# esquematico.net
KiCad netlist of a schematic drawn in Altium Designer
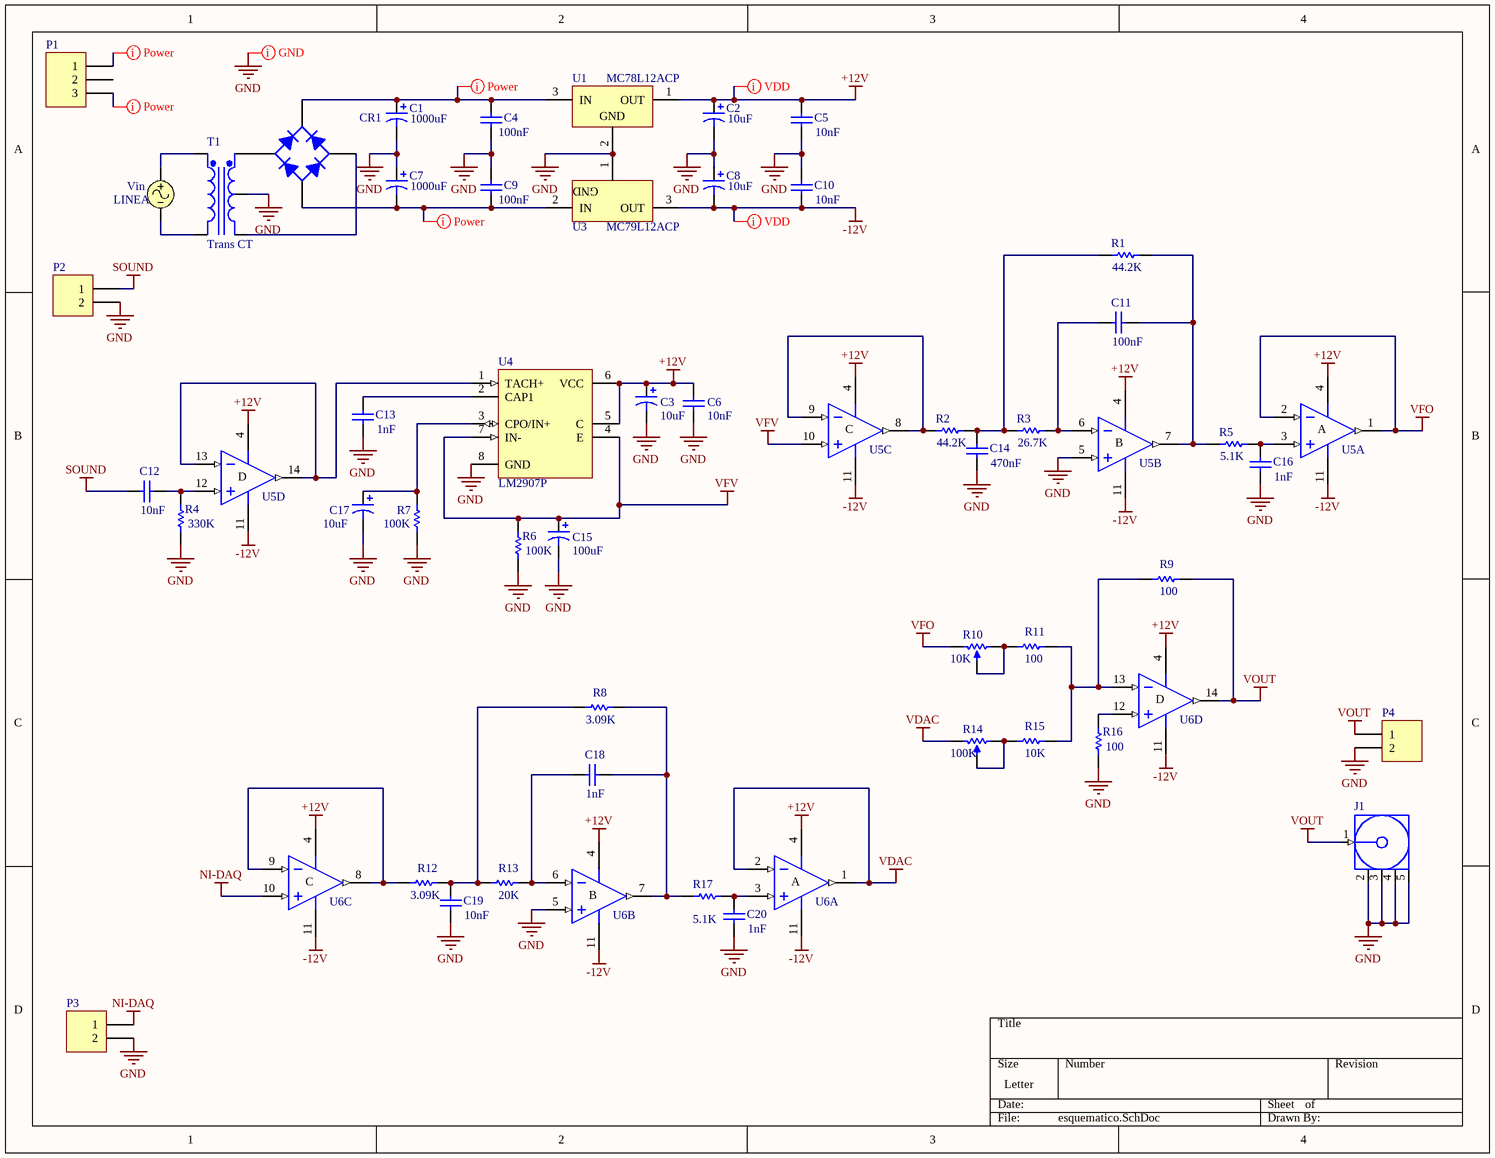
[diagram p0: esquematico.SchDoc]

(export (version "E")
  (design (tool "Eeschema 10.0.6"))
  (components
    (comp (ref "C1")
      (value "1000uF")
      (footprint "CAPPR5-10x20/H1.1")
      (description "Polarized Capacitor (Radial)")
      (fields (field (name "Comment") "Cap Pol1") (field (name "PUBLISHER") "Altium Limited"))
      (libsource (lib "Miscellaneous Devices") (part "Cap Pol1"))
    )
    (comp (ref "C2")
      (value "10uF")
      (footprint "CAPPR2-5x11")
      (description "Polarized Capacitor (Radial)")
      (fields (field (name "Comment") "Cap Pol1") (field (name "PUBLISHER") "Altium Limited"))
      (libsource (lib "Miscellaneous Devices") (part "Cap Pol1"))
    )
    (comp (ref "C3")
      (value "10uF")
      (footprint "CAPPR2-5x11")
      (description "Polarized Capacitor (Radial)")
      (fields (field (name "Comment") "Cap Pol1") (field (name "PUBLISHER") "Altium Limited"))
      (libsource (lib "Miscellaneous Devices") (part "Cap Pol1"))
    )
    (comp (ref "C4")
      (value "100nF")
      (footprint "CAPR2.54-4x2.5")
      (description "Capacitor")
      (fields (field (name "Comment") "Cap") (field (name "PUBLISHER") "Altium Limited"))
      (libsource (lib "Miscellaneous Devices") (part "Cap"))
    )
    (comp (ref "C5")
      (value "10nF")
      (footprint "CAPR2.54-4x2.5")
      (description "Capacitor")
      (fields (field (name "Comment") "Cap") (field (name "PUBLISHER") "Altium Limited"))
      (libsource (lib "Miscellaneous Devices") (part "Cap"))
    )
    (comp (ref "C6")
      (value "10nF")
      (footprint "CAPR2.54-4x2.5")
      (description "Capacitor")
      (fields (field (name "Comment") "Cap") (field (name "PUBLISHER") "Altium Limited"))
      (libsource (lib "Miscellaneous Devices") (part "Cap"))
    )
    (comp (ref "C7")
      (value "1000uF")
      (footprint "CAPPR5-10x20/H1.1")
      (description "Polarized Capacitor (Radial)")
      (fields (field (name "Comment") "Cap Pol1") (field (name "PUBLISHER") "Altium Limited"))
      (libsource (lib "Miscellaneous Devices") (part "Cap Pol1"))
    )
    (comp (ref "C8")
      (value "10uF")
      (footprint "CAPPR2-5x11")
      (description "Polarized Capacitor (Radial)")
      (fields (field (name "Comment") "Cap Pol1") (field (name "PUBLISHER") "Altium Limited"))
      (libsource (lib "Miscellaneous Devices") (part "Cap Pol1"))
    )
    (comp (ref "C9")
      (value "100nF")
      (footprint "CAPR2.54-4x2.5")
      (description "Capacitor")
      (fields (field (name "Comment") "Cap") (field (name "PUBLISHER") "Altium Limited"))
      (libsource (lib "Miscellaneous Devices") (part "Cap"))
    )
    (comp (ref "C10")
      (value "10nF")
      (footprint "CAPR2.54-4x2.5")
      (description "Capacitor")
      (fields (field (name "Comment") "Cap") (field (name "PUBLISHER") "Altium Limited"))
      (libsource (lib "Miscellaneous Devices") (part "Cap"))
    )
    (comp (ref "C11")
      (value "100nF")
      (footprint "CAPR2.54-4x2.5")
      (description "Capacitor")
      (fields (field (name "Comment") "Cap") (field (name "PUBLISHER") "Altium Limited"))
      (libsource (lib "Miscellaneous Devices") (part "Cap"))
    )
    (comp (ref "C12")
      (value "10nF")
      (footprint "CAPR2.54-4x2.5")
      (description "Capacitor")
      (fields (field (name "Comment") "Cap") (field (name "PUBLISHER") "Altium Limited"))
      (libsource (lib "Miscellaneous Devices") (part "Cap"))
    )
    (comp (ref "C13")
      (value "1nF")
      (footprint "CAPR5.08-4x2.5")
      (description "Capacitor")
      (fields (field (name "Comment") "Cap") (field (name "PUBLISHER") "Altium Limited"))
      (libsource (lib "Miscellaneous Devices") (part "Cap"))
    )
    (comp (ref "C14")
      (value "470nF")
      (footprint "CAPR5.08-4x2.5")
      (description "Capacitor")
      (fields (field (name "Comment") "Cap") (field (name "PUBLISHER") "Altium Limited"))
      (libsource (lib "Miscellaneous Devices") (part "Cap"))
    )
    (comp (ref "C15")
      (value "100uF")
      (footprint "CAPPR2.5-6.3x11")
      (description "Polarized Capacitor (Radial)")
      (fields (field (name "Comment") "Cap Pol1") (field (name "PUBLISHER") "Altium Limited"))
      (libsource (lib "Miscellaneous Devices") (part "Cap Pol1"))
    )
    (comp (ref "C16")
      (value "1nF")
      (footprint "CAPR5.08-5.1x2.5")
      (description "Capacitor")
      (fields (field (name "Comment") "Cap") (field (name "PUBLISHER") "Altium Limited"))
      (libsource (lib "Miscellaneous Devices") (part "Cap"))
    )
    (comp (ref "C17")
      (value "10uF")
      (footprint "CAPPR2-5x11")
      (description "Polarized Capacitor (Radial)")
      (fields (field (name "Comment") "Cap Pol1") (field (name "PUBLISHER") "Altium Limited"))
      (libsource (lib "Miscellaneous Devices") (part "Cap Pol1"))
    )
    (comp (ref "C18")
      (value "1nF")
      (footprint "CAPR5.08-5.1x2.5")
      (description "Capacitor")
      (fields (field (name "Comment") "Cap") (field (name "PUBLISHER") "Altium Limited"))
      (libsource (lib "Miscellaneous Devices") (part "Cap"))
    )
    (comp (ref "C19")
      (value "10nF")
      (footprint "CAPR2.54-4x2.5")
      (description "Capacitor")
      (fields (field (name "Comment") "Cap") (field (name "PUBLISHER") "Altium Limited"))
      (libsource (lib "Miscellaneous Devices") (part "Cap"))
    )
    (comp (ref "C20")
      (value "1nF")
      (footprint "CAPR5.08-5.1x2.5")
      (description "Capacitor")
      (fields (field (name "Comment") "Cap") (field (name "PUBLISHER") "Altium Limited"))
      (libsource (lib "Miscellaneous Devices") (part "Cap"))
    )
    (comp (ref "CR1")
      (value "2KBP005")
      (footprint "D-44")
      (description "2 Amp Single Phase Rectifier Bridge")
      (fields (field (name "PUBLISHER") "Altium Limited"))
      (libsource (lib "IR Rectifier - Bridge") (part "2KBP005"))
    )
    (comp (ref "J1")
      (value "COAX-F")
      (footprint "MCX5.08-H5")
      (fields (field (name "PUBLISHER") "Altium Limited"))
      (libsource (lib "Miscellaneous Connectors") (part "COAX-F"))
    )
    (comp (ref "P1")
      (value "Header 3")
      (footprint "HDR1X3")
      (description "Header, 3-Pin")
      (fields (field (name "PUBLISHER") "Altium Limited"))
      (libsource (lib "Miscellaneous Connectors") (part "Header 3"))
    )
    (comp (ref "P2")
      (value "Header 2")
      (footprint "HDR1X2")
      (description "Header, 2-Pin")
      (fields (field (name "PUBLISHER") "Altium Limited"))
      (libsource (lib "") (part "Header 2_1"))
    )
    (comp (ref "P3")
      (value "Header 2")
      (footprint "HDR1X2")
      (description "Header, 2-Pin")
      (fields (field (name "PUBLISHER") "Altium Limited"))
      (libsource (lib "") (part "Header 2_1"))
    )
    (comp (ref "P4")
      (value "Header 2")
      (footprint "HDR1X2")
      (description "Header, 2-Pin")
      (fields (field (name "PUBLISHER") "Altium Limited"))
      (libsource (lib "Miscellaneous Connectors") (part "Header 2"))
    )
    (comp (ref "R1")
      (value "44.2K")
      (footprint "AXIAL-0.3")
      (description "Resistor")
      (fields (field (name "Comment") "Res1") (field (name "PUBLISHER") "Altium Limited"))
      (libsource (lib "Miscellaneous Devices") (part "Res1"))
    )
    (comp (ref "R2")
      (value "44.2K")
      (footprint "AXIAL-0.3")
      (description "Resistor")
      (fields (field (name "Comment") "Res1") (field (name "PUBLISHER") "Altium Limited"))
      (libsource (lib "Miscellaneous Devices") (part "Res1"))
    )
    (comp (ref "R3")
      (value "26.7K")
      (footprint "AXIAL-0.3")
      (description "Resistor")
      (fields (field (name "Comment") "Res1") (field (name "PUBLISHER") "Altium Limited"))
      (libsource (lib "Miscellaneous Devices") (part "Res1"))
    )
    (comp (ref "R4")
      (value "330K")
      (footprint "AXIAL-0.3")
      (description "Resistor")
      (fields (field (name "Comment") "Res1") (field (name "PUBLISHER") "Altium Limited"))
      (libsource (lib "Miscellaneous Devices") (part "Res1"))
    )
    (comp (ref "R5")
      (value "5.1K")
      (footprint "AXIAL-0.3")
      (description "Resistor")
      (fields (field (name "Comment") "Res1") (field (name "PUBLISHER") "Altium Limited"))
      (libsource (lib "Miscellaneous Devices") (part "Res1"))
    )
    (comp (ref "R6")
      (value "100K")
      (footprint "AXIAL-0.3")
      (description "Resistor")
      (fields (field (name "Comment") "Res1") (field (name "PUBLISHER") "Altium Limited"))
      (libsource (lib "Miscellaneous Devices") (part "Res1"))
    )
    (comp (ref "R7")
      (value "100K")
      (footprint "AXIAL-0.3")
      (description "Resistor")
      (fields (field (name "Comment") "Res1") (field (name "PUBLISHER") "Altium Limited"))
      (libsource (lib "Miscellaneous Devices") (part "Res1"))
    )
    (comp (ref "R8")
      (value "3.09K")
      (footprint "AXIAL-0.3")
      (description "Resistor")
      (fields (field (name "Comment") "Res1") (field (name "PUBLISHER") "Altium Limited"))
      (libsource (lib "Miscellaneous Devices") (part "Res1"))
    )
    (comp (ref "R9")
      (value "100")
      (footprint "AXIAL-0.3")
      (description "Resistor")
      (fields (field (name "Comment") "Res1") (field (name "PUBLISHER") "Altium Limited"))
      (libsource (lib "Miscellaneous Devices") (part "Res1"))
    )
    (comp (ref "R10")
      (value "10K")
      (footprint "3006P")
      (description "Rectangular Trimmer Potentiometer")
      (fields (field (name "Comment") "RTrimPot"))
      (libsource (lib "libreria") (part "RTrimPot"))
    )
    (comp (ref "R11")
      (value "100")
      (footprint "AXIAL-0.3")
      (description "Resistor")
      (fields (field (name "Comment") "Res1") (field (name "PUBLISHER") "Altium Limited"))
      (libsource (lib "Miscellaneous Devices") (part "Res1"))
    )
    (comp (ref "R12")
      (value "3.09K")
      (footprint "AXIAL-0.3")
      (description "Resistor")
      (fields (field (name "Comment") "Res1") (field (name "PUBLISHER") "Altium Limited"))
      (libsource (lib "Miscellaneous Devices") (part "Res1"))
    )
    (comp (ref "R13")
      (value "20K")
      (footprint "AXIAL-0.3")
      (description "Resistor")
      (fields (field (name "Comment") "Res1") (field (name "PUBLISHER") "Altium Limited"))
      (libsource (lib "Miscellaneous Devices") (part "Res1"))
    )
    (comp (ref "R14")
      (value "100K")
      (footprint "3006P")
      (description "Rectangular Trimmer Potentiometer")
      (fields (field (name "Comment") "RTrimPot"))
      (libsource (lib "libreria") (part "RTrimPot"))
    )
    (comp (ref "R15")
      (value "10K")
      (footprint "AXIAL-0.3")
      (description "Resistor")
      (fields (field (name "Comment") "Res1") (field (name "PUBLISHER") "Altium Limited"))
      (libsource (lib "Miscellaneous Devices") (part "Res1"))
    )
    (comp (ref "R16")
      (value "100")
      (footprint "AXIAL-0.3")
      (description "Resistor")
      (fields (field (name "Comment") "Res1") (field (name "PUBLISHER") "Altium Limited"))
      (libsource (lib "Miscellaneous Devices") (part "Res1"))
    )
    (comp (ref "R17")
      (value "5.1K")
      (footprint "AXIAL-0.3")
      (description "Resistor")
      (fields (field (name "Comment") "Res1") (field (name "PUBLISHER") "Altium Limited"))
      (libsource (lib "Miscellaneous Devices") (part "Res1"))
    )
    (comp (ref "T1")
      (value "Trans CT")
      (footprint "TRF_5")
      (description "Center-Tapped Transformer (Coupled Inductor Model)")
      (fields (field (name "PUBLISHER") "Altium Limited"))
      (libsource (lib "Miscellaneous Devices") (part "Trans CT"))
    )
    (comp (ref "U1")
      (value "MC78L12ACP")
      (footprint "BCY-W3/W")
      (description "Three-Terminal Low Current Positive Voltage Regulator")
      (fields (field (name "PUBLISHER") "Altium Limited"))
      (libsource (lib "ON Semi Power Mgt Voltage Regulator") (part "MC78L12ACP"))
    )
    (comp (ref "U3")
      (value "MC79L12ACP")
      (footprint "BCY-W3/W")
      (description "Three-Terminal Low Current Negative Voltage Regulator")
      (fields (field (name "PUBLISHER") "Altium Limited"))
      (libsource (lib "ON Semi Power Mgt Voltage Regulator") (part "MC79L12ACP"))
    )
    (comp (ref "U4")
      (value "LM2907P")
      (footprint "P008")
      (description "Frequency-To-Voltage Converters")
      (fields (field (name "PUBLISHER") "Altium Limited"))
      (libsource (lib "TI Converter Frequency to Voltage") (part "LM2907P"))
    )
    (comp (ref "U5")
      (value "TL084CN")
      (footprint "DIP14")
      (description "General-Purpose J-FET Quad Operational Amplifier")
      (fields (field (name "PUBLISHER") "Altium Limited"))
      (libsource (lib "ST Operational Amplifier") (part "TL084CN"))
    )
    (comp (ref "U6")
      (value "TL084CN")
      (footprint "DIP14")
      (description "General-Purpose J-FET Quad Operational Amplifier")
      (fields (field (name "PUBLISHER") "Altium Limited"))
      (libsource (lib "ST Operational Amplifier") (part "TL084CN"))
    )
    (comp (ref "Vin")
      (value "LINEA")
      (description "Sinusoidal Voltage Source")
      (fields (field (name "PUBLISHER") "Altium Limited"))
      (libsource (lib "Simulation Sources") (part "VSIN"))
    )
  )
  (nets
    (net (code "1") (name "+12V") (class "Default")
      (node (ref "C2") (pin "1") (pinfunction "1_1") (pintype "passive"))
      (node (ref "C3") (pin "1") (pinfunction "1_1") (pintype "passive"))
      (node (ref "C5") (pin "1") (pinfunction "1_1") (pintype "passive"))
      (node (ref "C6") (pin "1") (pinfunction "1_1") (pintype "passive"))
      (node (ref "U1") (pin "1") (pinfunction "OUT_1") (pintype "power_in"))
      (node (ref "U4") (pin "5") (pinfunction "C_5") (pintype "passive"))
      (node (ref "U4") (pin "6") (pinfunction "VCC_6") (pintype "power_in"))
      (node (ref "U5") (pin "4") (pinfunction "V+_4") (pintype "power_in"))
      (node (ref "U6") (pin "4") (pinfunction "V+_4") (pintype "power_in"))
    )
    (net (code "2") (name "-12V") (class "Default")
      (node (ref "C10") (pin "1") (pinfunction "1_1") (pintype "passive"))
      (node (ref "C8") (pin "2") (pinfunction "2_2") (pintype "passive"))
      (node (ref "U3") (pin "3") (pinfunction "OUT_3") (pintype "power_in"))
      (node (ref "U5") (pin "11") (pinfunction "V-_11") (pintype "power_in"))
      (node (ref "U6") (pin "11") (pinfunction "V-_11") (pintype "power_in"))
    )
    (net (code "3") (name "GND") (class "Default")
      (node (ref "C1") (pin "2") (pinfunction "2_2") (pintype "passive"))
      (node (ref "C10") (pin "2") (pinfunction "2_2") (pintype "passive"))
      (node (ref "C13") (pin "1") (pinfunction "1_1") (pintype "passive"))
      (node (ref "C14") (pin "2") (pinfunction "2_2") (pintype "passive"))
      (node (ref "C15") (pin "2") (pinfunction "2_2") (pintype "passive"))
      (node (ref "C16") (pin "1") (pinfunction "1_1") (pintype "passive"))
      (node (ref "C17") (pin "2") (pinfunction "2_2") (pintype "passive"))
      (node (ref "C19") (pin "2") (pinfunction "2_2") (pintype "passive"))
      (node (ref "C2") (pin "2") (pinfunction "2_2") (pintype "passive"))
      (node (ref "C20") (pin "1") (pinfunction "1_1") (pintype "passive"))
      (node (ref "C3") (pin "2") (pinfunction "2_2") (pintype "passive"))
      (node (ref "C4") (pin "2") (pinfunction "2_2") (pintype "passive"))
      (node (ref "C5") (pin "2") (pinfunction "2_2") (pintype "passive"))
      (node (ref "C6") (pin "2") (pinfunction "2_2") (pintype "passive"))
      (node (ref "C7") (pin "1") (pinfunction "1_1") (pintype "passive"))
      (node (ref "C8") (pin "1") (pinfunction "1_1") (pintype "passive"))
      (node (ref "C9") (pin "2") (pinfunction "2_2") (pintype "passive"))
      (node (ref "J1") (pin "2") (pinfunction "GND_2") (pintype "power_in"))
      (node (ref "J1") (pin "3") (pinfunction "GND_3") (pintype "power_in"))
      (node (ref "J1") (pin "4") (pinfunction "GND_4") (pintype "power_in"))
      (node (ref "J1") (pin "5") (pinfunction "GND_5") (pintype "power_in"))
      (node (ref "P2") (pin "2") (pinfunction "2_2") (pintype "passive"))
      (node (ref "P3") (pin "2") (pinfunction "2_2") (pintype "passive"))
      (node (ref "P4") (pin "2") (pinfunction "2_2") (pintype "passive"))
      (node (ref "R16") (pin "1") (pinfunction "1_1") (pintype "passive"))
      (node (ref "R4") (pin "1") (pinfunction "1_1") (pintype "passive"))
      (node (ref "R6") (pin "1") (pinfunction "1_1") (pintype "passive"))
      (node (ref "R7") (pin "1") (pinfunction "1_1") (pintype "passive"))
      (node (ref "T1") (pin "4") (pinfunction "SecCT_4") (pintype "passive"))
      (node (ref "U1") (pin "2") (pinfunction "GND_2") (pintype "power_in"))
      (node (ref "U3") (pin "1") (pinfunction "GND_1") (pintype "power_in"))
      (node (ref "U4") (pin "8") (pinfunction "GND_8") (pintype "power_in"))
      (node (ref "U5") (pin "5") (pinfunction "IN+_5") (pintype "input"))
      (node (ref "U6") (pin "5") (pinfunction "IN+_5") (pintype "input"))
    )
    (net (code "4") (name "NI-DAQ") (class "Default")
      (node (ref "P3") (pin "1") (pinfunction "1_1") (pintype "passive"))
      (node (ref "U6") (pin "10") (pinfunction "IN+_10") (pintype "input"))
    )
    (net (code "5") (name "Net-(C14-Pad1)") (class "Default")
      (node (ref "C14") (pin "1") (pinfunction "1_1") (pintype "passive"))
      (node (ref "R1") (pin "1") (pinfunction "1_1") (pintype "passive"))
      (node (ref "R2") (pin "2") (pinfunction "2_2") (pintype "passive"))
      (node (ref "R3") (pin "1") (pinfunction "1_1") (pintype "passive"))
    )
    (net (code "6") (name "Net-(C19-Pad1)") (class "Default")
      (node (ref "C19") (pin "1") (pinfunction "1_1") (pintype "passive"))
      (node (ref "R12") (pin "2") (pinfunction "2_2") (pintype "passive"))
      (node (ref "R13") (pin "1") (pinfunction "1_1") (pintype "passive"))
      (node (ref "R8") (pin "1") (pinfunction "1_1") (pintype "passive"))
    )
    (net (code "7") (name "Net-(CR1-A)") (class "Default")
      (node (ref "C7") (pin "2") (pinfunction "2_2") (pintype "passive"))
      (node (ref "C9") (pin "1") (pinfunction "1_1") (pintype "passive"))
      (node (ref "CR1") (pin "4") (pinfunction "A_4") (pintype "passive"))
      (node (ref "U3") (pin "2") (pinfunction "IN_2") (pintype "power_in"))
    )
    (net (code "8") (name "Net-(CR1-K)") (class "Default")
      (node (ref "C1") (pin "1") (pinfunction "1_1") (pintype "passive"))
      (node (ref "C4") (pin "1") (pinfunction "1_1") (pintype "passive"))
      (node (ref "CR1") (pin "1") (pinfunction "K_1") (pintype "passive"))
      (node (ref "U1") (pin "3") (pinfunction "IN_3") (pintype "power_in"))
    )
    (net (code "9") (name "Net-(R10-Pad2)") (class "Default")
      (node (ref "R10") (pin "2") (pinfunction "2_2") (pintype "passive"))
      (node (ref "R10") (pin "3") (pinfunction "3_3") (pintype "passive"))
      (node (ref "R11") (pin "1") (pinfunction "1_1") (pintype "passive"))
    )
    (net (code "10") (name "Net-(R14-Pad2)") (class "Default")
      (node (ref "R14") (pin "2") (pinfunction "2_2") (pintype "passive"))
      (node (ref "R14") (pin "3") (pinfunction "3_3") (pintype "passive"))
      (node (ref "R15") (pin "1") (pinfunction "1_1") (pintype "passive"))
    )
    (net (code "11") (name "Net-(T1-Pri+)") (class "Default")
      (node (ref "T1") (pin "1") (pinfunction "Pri+_1") (pintype "passive"))
      (node (ref "Vin") (pin "1") (pinfunction "1_1") (pintype "passive"))
    )
    (net (code "12") (name "Net-(T1-Pri-)") (class "Default")
      (node (ref "T1") (pin "2") (pinfunction "Pri-_2") (pintype "passive"))
      (node (ref "Vin") (pin "2") (pinfunction "2_2") (pintype "passive"))
    )
    (net (code "13") (name "Net-(T1-Sec+)") (class "Default")
      (node (ref "CR1") (pin "2") (pinfunction "C_2") (pintype "passive"))
      (node (ref "T1") (pin "3") (pinfunction "Sec+_3") (pintype "passive"))
    )
    (net (code "14") (name "Net-(T1-Sec-)") (class "Default")
      (node (ref "CR1") (pin "3") (pinfunction "C_3") (pintype "passive"))
      (node (ref "T1") (pin "5") (pinfunction "Sec-_5") (pintype "passive"))
    )
    (net (code "15") (name "Net-(U4-CAP1)") (class "Default")
      (node (ref "C13") (pin "2") (pinfunction "2_2") (pintype "passive"))
      (node (ref "U4") (pin "2") (pinfunction "CAP1_2") (pintype "passive"))
    )
    (net (code "16") (name "Net-(U4-CPO{slash}IN+)") (class "Default")
      (node (ref "C17") (pin "1") (pinfunction "1_1") (pintype "passive"))
      (node (ref "R7") (pin "2") (pinfunction "2_2") (pintype "passive"))
      (node (ref "U4") (pin "3") (pinfunction "CPO/IN+_3") (pintype "bidirectional"))
    )
    (net (code "17") (name "Net-(U4-TACH+)") (class "Default")
      (node (ref "U4") (pin "1") (pinfunction "TACH+_1") (pintype "input"))
      (node (ref "U5") (pin "13") (pinfunction "IN-_13") (pintype "input"))
      (node (ref "U5") (pin "14") (pinfunction "OUT_14") (pintype "output"))
    )
    (net (code "18") (name "Net-(U5A-IN+)") (class "Default")
      (node (ref "C16") (pin "2") (pinfunction "2_2") (pintype "passive"))
      (node (ref "R5") (pin "2") (pinfunction "2_2") (pintype "passive"))
      (node (ref "U5") (pin "3") (pinfunction "IN+_3") (pintype "input"))
    )
    (net (code "19") (name "Net-(U5B-IN-)") (class "Default")
      (node (ref "C11") (pin "2") (pinfunction "2_2") (pintype "passive"))
      (node (ref "R3") (pin "2") (pinfunction "2_2") (pintype "passive"))
      (node (ref "U5") (pin "6") (pinfunction "IN-_6") (pintype "input"))
    )
    (net (code "20") (name "Net-(U5B-OUT)") (class "Default")
      (node (ref "C11") (pin "1") (pinfunction "1_1") (pintype "passive"))
      (node (ref "R1") (pin "2") (pinfunction "2_2") (pintype "passive"))
      (node (ref "R5") (pin "1") (pinfunction "1_1") (pintype "passive"))
      (node (ref "U5") (pin "7") (pinfunction "OUT_7") (pintype "output"))
    )
    (net (code "21") (name "Net-(U5C-IN-)") (class "Default")
      (node (ref "R2") (pin "1") (pinfunction "1_1") (pintype "passive"))
      (node (ref "U5") (pin "8") (pinfunction "OUT_8") (pintype "output"))
      (node (ref "U5") (pin "9") (pinfunction "IN-_9") (pintype "input"))
    )
    (net (code "22") (name "Net-(U5D-IN+)") (class "Default")
      (node (ref "C12") (pin "1") (pinfunction "1_1") (pintype "passive"))
      (node (ref "R4") (pin "2") (pinfunction "2_2") (pintype "passive"))
      (node (ref "U5") (pin "12") (pinfunction "IN+_12") (pintype "input"))
    )
    (net (code "23") (name "Net-(U6A-IN+)") (class "Default")
      (node (ref "C20") (pin "2") (pinfunction "2_2") (pintype "passive"))
      (node (ref "R17") (pin "2") (pinfunction "2_2") (pintype "passive"))
      (node (ref "U6") (pin "3") (pinfunction "IN+_3") (pintype "input"))
    )
    (net (code "24") (name "Net-(U6B-IN-)") (class "Default")
      (node (ref "C18") (pin "2") (pinfunction "2_2") (pintype "passive"))
      (node (ref "R13") (pin "2") (pinfunction "2_2") (pintype "passive"))
      (node (ref "U6") (pin "6") (pinfunction "IN-_6") (pintype "input"))
    )
    (net (code "25") (name "Net-(U6B-OUT)") (class "Default")
      (node (ref "C18") (pin "1") (pinfunction "1_1") (pintype "passive"))
      (node (ref "R17") (pin "1") (pinfunction "1_1") (pintype "passive"))
      (node (ref "R8") (pin "2") (pinfunction "2_2") (pintype "passive"))
      (node (ref "U6") (pin "7") (pinfunction "OUT_7") (pintype "output"))
    )
    (net (code "26") (name "Net-(U6C-IN-)") (class "Default")
      (node (ref "R12") (pin "1") (pinfunction "1_1") (pintype "passive"))
      (node (ref "U6") (pin "8") (pinfunction "OUT_8") (pintype "output"))
      (node (ref "U6") (pin "9") (pinfunction "IN-_9") (pintype "input"))
    )
    (net (code "27") (name "Net-(U6D-IN+)") (class "Default")
      (node (ref "R16") (pin "2") (pinfunction "2_2") (pintype "passive"))
      (node (ref "U6") (pin "12") (pinfunction "IN+_12") (pintype "input"))
    )
    (net (code "28") (name "Net-(U6D-IN-)") (class "Default")
      (node (ref "R11") (pin "2") (pinfunction "2_2") (pintype "passive"))
      (node (ref "R15") (pin "2") (pinfunction "2_2") (pintype "passive"))
      (node (ref "R9") (pin "1") (pinfunction "1_1") (pintype "passive"))
      (node (ref "U6") (pin "13") (pinfunction "IN-_13") (pintype "input"))
    )
    (net (code "29") (name "SOUND") (class "Default")
      (node (ref "C12") (pin "2") (pinfunction "2_2") (pintype "passive"))
      (node (ref "P2") (pin "1") (pinfunction "1_1") (pintype "passive"))
    )
    (net (code "30") (name "VDAC") (class "Default")
      (node (ref "R14") (pin "1") (pinfunction "1_1") (pintype "passive"))
      (node (ref "U6") (pin "1") (pinfunction "OUT_1") (pintype "output"))
      (node (ref "U6") (pin "2") (pinfunction "IN-_2") (pintype "input"))
    )
    (net (code "31") (name "VFO") (class "Default")
      (node (ref "R10") (pin "1") (pinfunction "1_1") (pintype "passive"))
      (node (ref "U5") (pin "1") (pinfunction "OUT_1") (pintype "output"))
      (node (ref "U5") (pin "2") (pinfunction "IN-_2") (pintype "input"))
    )
    (net (code "32") (name "VFV") (class "Default")
      (node (ref "C15") (pin "1") (pinfunction "1_1") (pintype "passive"))
      (node (ref "R6") (pin "2") (pinfunction "2_2") (pintype "passive"))
      (node (ref "U4") (pin "4") (pinfunction "E_4") (pintype "passive"))
      (node (ref "U4") (pin "7") (pinfunction "IN-_7") (pintype "input"))
      (node (ref "U5") (pin "10") (pinfunction "IN+_10") (pintype "input"))
    )
    (net (code "33") (name "VOUT") (class "Default")
      (node (ref "J1") (pin "1") (pinfunction "Signal_1") (pintype "input"))
      (node (ref "P4") (pin "1") (pinfunction "1_1") (pintype "passive"))
      (node (ref "R9") (pin "2") (pinfunction "2_2") (pintype "passive"))
      (node (ref "U6") (pin "14") (pinfunction "OUT_14") (pintype "output"))
    )
    (net (code "34") (name "unconnected-(P1-Pad1)") (class "Default")
      (node (ref "P1") (pin "1") (pinfunction "1_1") (pintype "passive"))
    )
    (net (code "35") (name "unconnected-(P1-Pad2)") (class "Default")
      (node (ref "P1") (pin "2") (pinfunction "2_2") (pintype "passive"))
    )
    (net (code "36") (name "unconnected-(P1-Pad3)") (class "Default")
      (node (ref "P1") (pin "3") (pinfunction "3_3") (pintype "passive"))
    )
  )
)
